# contador_geiger.net
KiCad netlist of a schematic drawn in Altium Designer
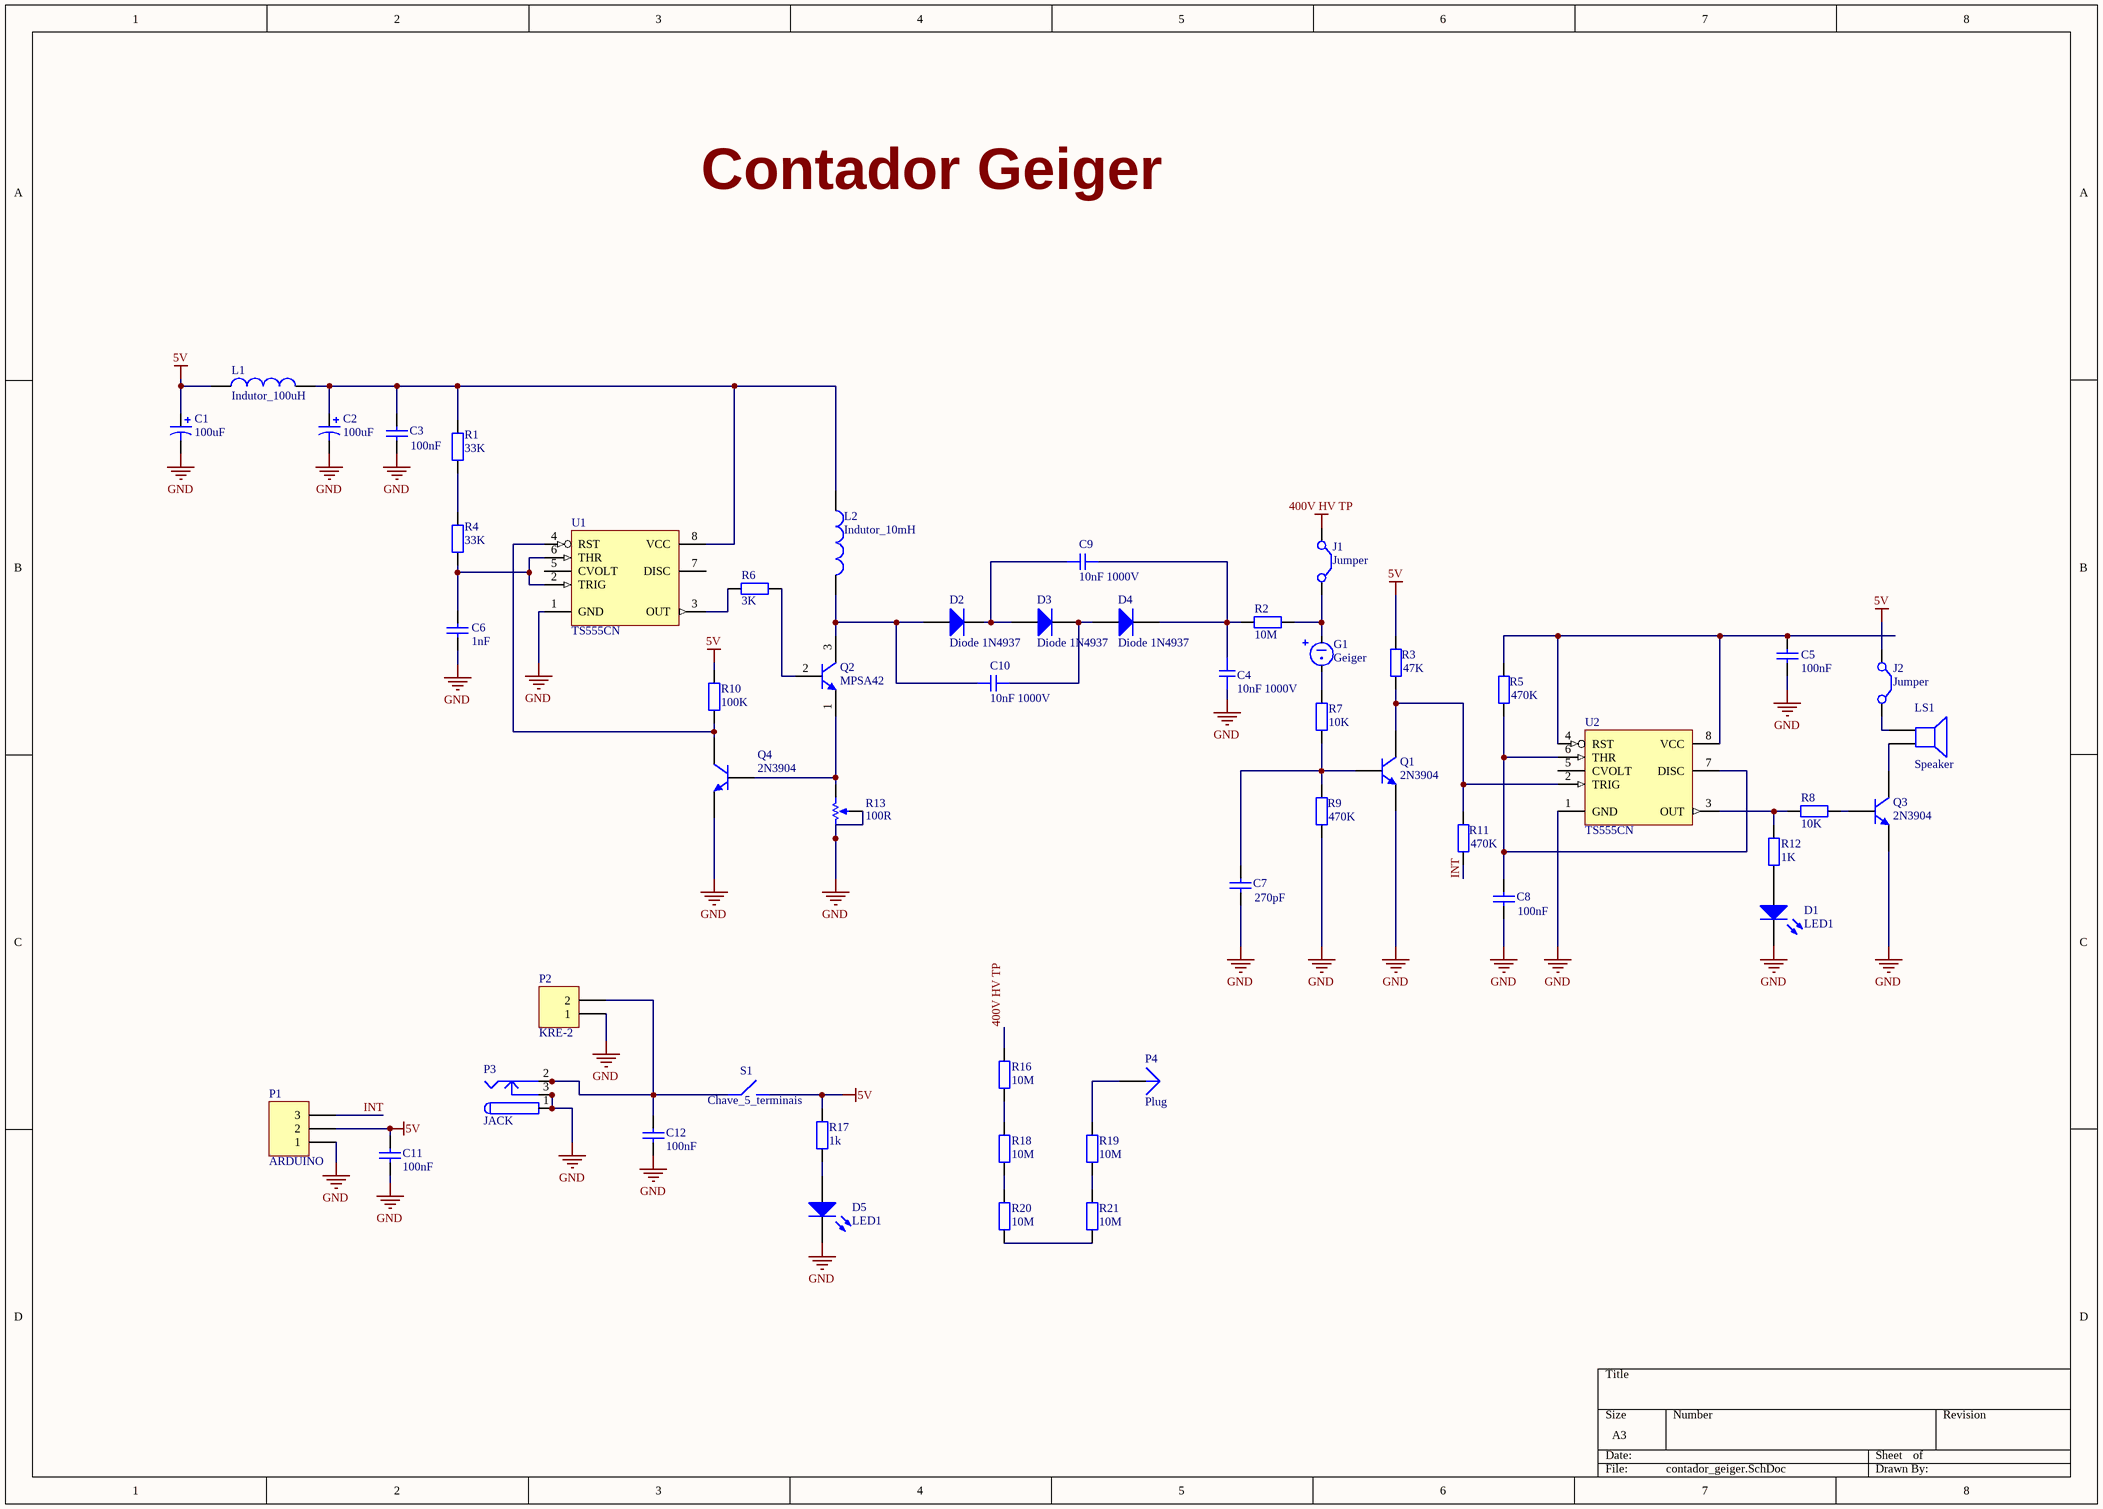
[diagram p0: contador_geiger.SchDoc]

(export (version "E")
  (design (tool "Eeschema 10.0.6"))
  (components
    (comp (ref "C1")
      (value "100uF")
      (footprint "RB7.6-15")
      (description "Polarized Capacitor (Radial)")
      (fields (field (name "Comment") "Cap Pol1") (field (name "PUBLISHER") "Altium Limited"))
      (libsource (lib "Miscellaneous Devices") (part "Cap Pol1"))
    )
    (comp (ref "C2")
      (value "100uF")
      (footprint "RB7.6-15")
      (description "Polarized Capacitor (Radial)")
      (fields (field (name "Comment") "Cap Pol1") (field (name "PUBLISHER") "Altium Limited"))
      (libsource (lib "Miscellaneous Devices") (part "Cap Pol1"))
    )
    (comp (ref "C3")
      (value "100nF")
      (footprint "RAD-0.3")
      (description "Capacitor")
      (fields (field (name "Comment") "Cap") (field (name "PUBLISHER") "Altium Limited"))
      (libsource (lib "Miscellaneous Devices") (part "Cap"))
    )
    (comp (ref "C4")
      (value "10nF 1000V")
      (footprint "Cap_10nF_1000V")
      (libsource (lib "Schlib1") (part "Capacitor_10n/1000V"))
    )
    (comp (ref "C5")
      (value "100nF")
      (footprint "RAD-0.3")
      (description "Capacitor")
      (fields (field (name "Comment") "Cap") (field (name "PUBLISHER") "Altium Limited"))
      (libsource (lib "Miscellaneous Devices") (part "Cap"))
    )
    (comp (ref "C6")
      (value "1nF")
      (footprint "RAD-0.3")
      (description "Capacitor")
      (fields (field (name "Comment") "Cap") (field (name "PUBLISHER") "Altium Limited"))
      (libsource (lib "Miscellaneous Devices") (part "Cap"))
    )
    (comp (ref "C7")
      (value "270pF")
      (footprint "RAD-0.3")
      (description "Capacitor")
      (fields (field (name "Comment") "Cap") (field (name "PUBLISHER") "Altium Limited"))
      (libsource (lib "Miscellaneous Devices") (part "Cap"))
    )
    (comp (ref "C8")
      (value "100nF")
      (footprint "RAD-0.3")
      (description "Capacitor")
      (fields (field (name "Comment") "Cap") (field (name "PUBLISHER") "Altium Limited"))
      (libsource (lib "Miscellaneous Devices") (part "Cap"))
    )
    (comp (ref "C9")
      (value "10nF 1000V")
      (footprint "Cap_10nF_1000V")
      (libsource (lib "Schlib1") (part "Capacitor_10n/1000V"))
    )
    (comp (ref "C10")
      (value "10nF 1000V")
      (footprint "Cap_10nF_1000V")
      (libsource (lib "Schlib1") (part "Capacitor_10n/1000V"))
    )
    (comp (ref "C11")
      (value "100nF")
      (footprint "RAD-0.3")
      (description "Capacitor")
      (fields (field (name "Comment") "Cap") (field (name "PUBLISHER") "Altium Limited"))
      (libsource (lib "Miscellaneous Devices") (part "Cap"))
    )
    (comp (ref "C12")
      (value "100nF")
      (footprint "RAD-0.3")
      (description "Capacitor")
      (fields (field (name "Comment") "Cap") (field (name "PUBLISHER") "Altium Limited"))
      (libsource (lib "Miscellaneous Devices") (part "Cap"))
    )
    (comp (ref "D1")
      (value "LED1")
      (footprint "LED-0")
      (description "Typical INFRARED GaAs LED")
      (fields (field (name "PUBLISHER") "Altium Limited"))
      (libsource (lib "Miscellaneous Devices") (part "LED0"))
    )
    (comp (ref "D2")
      (value "Diode 1N4937")
      (footprint "DO-41")
      (description "1 Amp Fast Recovery Rectifier")
      (fields (field (name "PUBLISHER") "Altium Limited"))
      (libsource (lib "Miscellaneous Devices") (part "Diode 1N4934"))
    )
    (comp (ref "D3")
      (value "Diode 1N4937")
      (footprint "DO-41")
      (description "1 Amp Fast Recovery Rectifier")
      (fields (field (name "PUBLISHER") "Altium Limited"))
      (libsource (lib "Miscellaneous Devices") (part "Diode 1N4934"))
    )
    (comp (ref "D4")
      (value "Diode 1N4937")
      (footprint "DO-41")
      (description "1 Amp Fast Recovery Rectifier")
      (fields (field (name "PUBLISHER") "Altium Limited"))
      (libsource (lib "Miscellaneous Devices") (part "Diode 1N4934"))
    )
    (comp (ref "D5")
      (value "LED1")
      (footprint "LED-0")
      (description "Typical INFRARED GaAs LED")
      (fields (field (name "PUBLISHER") "Altium Limited"))
      (libsource (lib "Miscellaneous Devices") (part "LED0"))
    )
    (comp (ref "G1")
      (value "Geiger")
      (footprint "Tubo Geiger")
      (libsource (lib "Schlib1") (part "Tubo_Geiger"))
    )
    (comp (ref "J1")
      (value "Jumper")
      (footprint "RAD-0.2")
      (description "Jumper Wire")
      (fields (field (name "PUBLISHER") "Altium Limited"))
      (libsource (lib "Miscellaneous Devices") (part "Jumper"))
    )
    (comp (ref "J2")
      (value "Jumper")
      (footprint "RAD-0.2")
      (description "Jumper Wire")
      (fields (field (name "PUBLISHER") "Altium Limited"))
      (libsource (lib "Miscellaneous Devices") (part "Jumper"))
    )
    (comp (ref "L1")
      (value "Indutor_100uH")
      (footprint "Indutor_100uH")
      (libsource (lib "Schlib1") (part "Indutor_100uH"))
    )
    (comp (ref "L2")
      (value "Indutor_10mH")
      (footprint "Indutor_10mH")
      (libsource (lib "Schlib1") (part "Indutor_10mH"))
    )
    (comp (ref "LS1")
      (value "Speaker")
      (footprint "PIN2")
      (description "Loudspeaker")
      (fields (field (name "PUBLISHER") "Altium Limited"))
      (libsource (lib "Miscellaneous Devices") (part "Speaker"))
    )
    (comp (ref "P1")
      (value "ARDUINO")
      (footprint "HDR1X3")
      (description "Header, 3-Pin")
      (fields (field (name "PUBLISHER") "Altium Limited"))
      (libsource (lib "Miscellaneous Connectors") (part "Header 3"))
    )
    (comp (ref "P2")
      (value "KRE-2")
      (footprint "HDR1X2")
      (description "Header, 2-Pin")
      (fields (field (name "PUBLISHER") "Altium Limited"))
      (libsource (lib "Miscellaneous Connectors") (part "Header 2"))
    )
    (comp (ref "P3")
      (value "JACK")
      (footprint "KLD-0202")
      (description "Low Voltage Power Supply Connector")
      (fields (field (name "PUBLISHER") "Altium Limited"))
      (libsource (lib "Miscellaneous Connectors") (part "PWR2.5"))
    )
    (comp (ref "P4")
      (value "Plug")
      (footprint "PIN1")
      (fields (field (name "PUBLISHER") "Altium Limited"))
      (libsource (lib "Miscellaneous Connectors") (part "Plug"))
    )
    (comp (ref "Q1")
      (value "2N3904")
      (footprint "TO-92A")
      (description "NPN General Purpose Amplifier")
      (fields (field (name "PUBLISHER") "Altium Limited"))
      (libsource (lib "Miscellaneous Devices") (part "2N3904"))
    )
    (comp (ref "Q2")
      (value "MPSA42")
      (footprint "ONSC-TO-92-3-29-11")
      (description "High Voltage Transistor, NPN Silicon, 3-Pin TO-92, Bulk Box")
      (fields (field (name "MANUFACTURER") "On Semiconductor"))
      (libsource (lib "ON Semi General Purpose Transistors") (part "MPSA42"))
    )
    (comp (ref "Q3")
      (value "2N3904")
      (footprint "TO-92A")
      (description "NPN General Purpose Amplifier")
      (fields (field (name "PUBLISHER") "Altium Limited"))
      (libsource (lib "Miscellaneous Devices") (part "2N3904"))
    )
    (comp (ref "Q4")
      (value "2N3904")
      (footprint "TO-92A")
      (description "NPN General Purpose Amplifier")
      (fields (field (name "PUBLISHER") "Altium Limited"))
      (libsource (lib "Miscellaneous Devices") (part "2N3904"))
    )
    (comp (ref "R1")
      (value "33K")
      (footprint "AXIAL-0.4")
      (description "Resistor")
      (fields (field (name "Comment") "Res2") (field (name "PUBLISHER") "Altium Limited"))
      (libsource (lib "Miscellaneous Devices") (part "Res2"))
    )
    (comp (ref "R2")
      (value "10M")
      (footprint "AXIAL-0.4")
      (description "Resistor")
      (fields (field (name "Comment") "Res2") (field (name "PUBLISHER") "Altium Limited"))
      (libsource (lib "") (part "Res2_2"))
    )
    (comp (ref "R3")
      (value "47K")
      (footprint "AXIAL-0.4")
      (description "Resistor")
      (fields (field (name "Comment") "Res2") (field (name "PUBLISHER") "Altium Limited"))
      (libsource (lib "Miscellaneous Devices") (part "Res2"))
    )
    (comp (ref "R4")
      (value "33K")
      (footprint "AXIAL-0.4")
      (description "Resistor")
      (fields (field (name "Comment") "Res2") (field (name "PUBLISHER") "Altium Limited"))
      (libsource (lib "Miscellaneous Devices") (part "Res2"))
    )
    (comp (ref "R5")
      (value "470K")
      (footprint "AXIAL-0.4")
      (description "Resistor")
      (fields (field (name "Comment") "Res2") (field (name "PUBLISHER") "Altium Limited"))
      (libsource (lib "Miscellaneous Devices") (part "Res2"))
    )
    (comp (ref "R6")
      (value "3K")
      (footprint "AXIAL-0.4")
      (description "Resistor")
      (fields (field (name "Comment") "Res2") (field (name "PUBLISHER") "Altium Limited"))
      (libsource (lib "") (part "Res2_2"))
    )
    (comp (ref "R7")
      (value "10K")
      (footprint "AXIAL-0.4")
      (description "Resistor")
      (fields (field (name "Comment") "Res2") (field (name "PUBLISHER") "Altium Limited"))
      (libsource (lib "Miscellaneous Devices") (part "Res2"))
    )
    (comp (ref "R8")
      (value "10K")
      (footprint "AXIAL-0.4")
      (description "Resistor")
      (fields (field (name "Comment") "Res2") (field (name "PUBLISHER") "Altium Limited"))
      (libsource (lib "") (part "Res2_1"))
    )
    (comp (ref "R9")
      (value "470K")
      (footprint "AXIAL-0.4")
      (description "Resistor")
      (fields (field (name "Comment") "Res2") (field (name "PUBLISHER") "Altium Limited"))
      (libsource (lib "Miscellaneous Devices") (part "Res2"))
    )
    (comp (ref "R10")
      (value "100K")
      (footprint "AXIAL-0.4")
      (description "Resistor")
      (fields (field (name "Comment") "Res2") (field (name "PUBLISHER") "Altium Limited"))
      (libsource (lib "Miscellaneous Devices") (part "Res2"))
    )
    (comp (ref "R11")
      (value "470K")
      (footprint "AXIAL-0.4")
      (description "Resistor")
      (fields (field (name "Comment") "Res2") (field (name "PUBLISHER") "Altium Limited"))
      (libsource (lib "Miscellaneous Devices") (part "Res2"))
    )
    (comp (ref "R12")
      (value "1K")
      (footprint "AXIAL-0.4")
      (description "Resistor")
      (fields (field (name "Comment") "Res2") (field (name "PUBLISHER") "Altium Limited"))
      (libsource (lib "Miscellaneous Devices") (part "Res2"))
    )
    (comp (ref "R13")
      (value "100R")
      (footprint "VR5")
      (description "Potentiometer")
      (fields (field (name "Comment") "RPot") (field (name "PUBLISHER") "Altium Limited"))
      (libsource (lib "Miscellaneous Devices") (part "RPot"))
    )
    (comp (ref "R16")
      (value "10M")
      (footprint "AXIAL-0.4")
      (description "Resistor")
      (fields (field (name "Comment") "Res2") (field (name "PUBLISHER") "Altium Limited"))
      (libsource (lib "Miscellaneous Devices") (part "Res2"))
    )
    (comp (ref "R17")
      (value "1k")
      (footprint "AXIAL-0.4")
      (description "Resistor")
      (fields (field (name "Comment") "Res2") (field (name "PUBLISHER") "Altium Limited"))
      (libsource (lib "Miscellaneous Devices") (part "Res2"))
    )
    (comp (ref "R18")
      (value "10M")
      (footprint "AXIAL-0.4")
      (description "Resistor")
      (fields (field (name "Comment") "Res2") (field (name "PUBLISHER") "Altium Limited"))
      (libsource (lib "Miscellaneous Devices") (part "Res2"))
    )
    (comp (ref "R19")
      (value "10M")
      (footprint "AXIAL-0.4")
      (description "Resistor")
      (fields (field (name "Comment") "Res2") (field (name "PUBLISHER") "Altium Limited"))
      (libsource (lib "Miscellaneous Devices") (part "Res2"))
    )
    (comp (ref "R20")
      (value "10M")
      (footprint "AXIAL-0.4")
      (description "Resistor")
      (fields (field (name "Comment") "Res2") (field (name "PUBLISHER") "Altium Limited"))
      (libsource (lib "Miscellaneous Devices") (part "Res2"))
    )
    (comp (ref "R21")
      (value "10M")
      (footprint "AXIAL-0.4")
      (description "Resistor")
      (fields (field (name "Comment") "Res2") (field (name "PUBLISHER") "Altium Limited"))
      (libsource (lib "Miscellaneous Devices") (part "Res2"))
    )
    (comp (ref "S1")
      (value "Chave_5_terminais")
      (footprint "Chave_5_terminais")
      (libsource (lib "Schlib1") (part "Chave_5_terminais"))
    )
    (comp (ref "U1")
      (value "TS555CN")
      (footprint "DIP8")
      (description "Low-Power Single CMOS Timer")
      (fields (field (name "PUBLISHER") "Altium Limited"))
      (libsource (lib "ST Analog Timer Circuit") (part "TS555CN"))
    )
    (comp (ref "U2")
      (value "TS555CN")
      (footprint "DIP8")
      (description "Low-Power Single CMOS Timer")
      (fields (field (name "PUBLISHER") "Altium Limited"))
      (libsource (lib "ST Analog Timer Circuit") (part "TS555CN"))
    )
  )
  (nets
    (net (code "1") (name "/INT") (class "Default")
      (node (ref "P1") (pin "3") (pinfunction "3_3") (pintype "passive"))
      (node (ref "R11") (pin "1") (pinfunction "1_1") (pintype "passive"))
    )
    (net (code "2") (name "5V") (class "Default")
      (node (ref "C1") (pin "1") (pinfunction "1_1") (pintype "passive"))
      (node (ref "C11") (pin "1") (pinfunction "1_1") (pintype "passive"))
      (node (ref "J2") (pin "1") (pinfunction "C1_1") (pintype "passive"))
      (node (ref "L1") (pin "1") (pinfunction "1_1") (pintype "passive"))
      (node (ref "P1") (pin "2") (pinfunction "2_2") (pintype "passive"))
      (node (ref "R10") (pin "2") (pinfunction "2_2") (pintype "passive"))
      (node (ref "R17") (pin "2") (pinfunction "2_2") (pintype "passive"))
      (node (ref "R3") (pin "2") (pinfunction "2_2") (pintype "passive"))
      (node (ref "S1") (pin "2") (pinfunction "2_2") (pintype "passive"))
    )
    (net (code "3") (name "400V HV TP") (class "Default")
      (node (ref "J1") (pin "1") (pinfunction "C1_1") (pintype "passive"))
      (node (ref "R16") (pin "2") (pinfunction "2_2") (pintype "passive"))
    )
    (net (code "4") (name "GND") (class "Default")
      (node (ref "C1") (pin "2") (pinfunction "2_2") (pintype "passive"))
      (node (ref "C11") (pin "2") (pinfunction "2_2") (pintype "passive"))
      (node (ref "C12") (pin "2") (pinfunction "2_2") (pintype "passive"))
      (node (ref "C2") (pin "2") (pinfunction "2_2") (pintype "passive"))
      (node (ref "C3") (pin "1") (pinfunction "1_1") (pintype "passive"))
      (node (ref "C4") (pin "1") (pinfunction "1_1") (pintype "passive"))
      (node (ref "C5") (pin "1") (pinfunction "1_1") (pintype "passive"))
      (node (ref "C6") (pin "1") (pinfunction "1_1") (pintype "passive"))
      (node (ref "C7") (pin "1") (pinfunction "1_1") (pintype "passive"))
      (node (ref "C8") (pin "1") (pinfunction "1_1") (pintype "passive"))
      (node (ref "D1") (pin "2") (pinfunction "K_2") (pintype "passive"))
      (node (ref "D5") (pin "2") (pinfunction "K_2") (pintype "passive"))
      (node (ref "P1") (pin "1") (pinfunction "1_1") (pintype "passive"))
      (node (ref "P2") (pin "1") (pinfunction "1_1") (pintype "passive"))
      (node (ref "P3") (pin "1") (pinfunction "1_1") (pintype "power_in"))
      (node (ref "P3") (pin "1A") (pinfunction "1A_1A") (pintype "power_in"))
      (node (ref "P3") (pin "1B") (pinfunction "1B_1B") (pintype "power_in"))
      (node (ref "P3") (pin "3") (pinfunction "3_3") (pintype "power_in"))
      (node (ref "P3") (pin "3A") (pinfunction "3A_3A") (pintype "power_in"))
      (node (ref "P3") (pin "3B") (pinfunction "3B_3B") (pintype "power_in"))
      (node (ref "Q1") (pin "1") (pinfunction "E_1") (pintype "passive"))
      (node (ref "Q3") (pin "1") (pinfunction "E_1") (pintype "passive"))
      (node (ref "Q4") (pin "1") (pinfunction "E_1") (pintype "passive"))
      (node (ref "R13") (pin "2") (pinfunction "BOT_2") (pintype "passive"))
      (node (ref "R13") (pin "3") (pinfunction "TAP_3") (pintype "passive"))
      (node (ref "R9") (pin "1") (pinfunction "1_1") (pintype "passive"))
      (node (ref "U1") (pin "1") (pinfunction "GND_1") (pintype "power_in"))
      (node (ref "U2") (pin "1") (pinfunction "GND_1") (pintype "power_in"))
    )
    (net (code "5") (name "Net-(C12-Pad1)") (class "Default")
      (node (ref "C12") (pin "1") (pinfunction "1_1") (pintype "passive"))
      (node (ref "P2") (pin "2") (pinfunction "2_2") (pintype "passive"))
      (node (ref "P3") (pin "2") (pinfunction "2_2") (pintype "power_in"))
      (node (ref "P3") (pin "2A") (pinfunction "2A_2A") (pintype "power_in"))
      (node (ref "P3") (pin "2B") (pinfunction "2B_2B") (pintype "power_in"))
      (node (ref "S1") (pin "1") (pinfunction "1_1") (pintype "passive"))
    )
    (net (code "6") (name "Net-(D1-A)") (class "Default")
      (node (ref "D1") (pin "1") (pinfunction "A_1") (pintype "passive"))
      (node (ref "R12") (pin "1") (pinfunction "1_1") (pintype "passive"))
    )
    (net (code "7") (name "Net-(D2-A)") (class "Default")
      (node (ref "C10") (pin "1") (pinfunction "1_1") (pintype "passive"))
      (node (ref "D2") (pin "1") (pinfunction "A_1") (pintype "passive"))
      (node (ref "L2") (pin "2") (pinfunction "2_2") (pintype "passive"))
      (node (ref "Q2") (pin "3") (pinfunction "C_3") (pintype "passive"))
    )
    (net (code "8") (name "Net-(D2-K)") (class "Default")
      (node (ref "C9") (pin "1") (pinfunction "1_1") (pintype "passive"))
      (node (ref "D2") (pin "2") (pinfunction "K_2") (pintype "passive"))
      (node (ref "D3") (pin "1") (pinfunction "A_1") (pintype "passive"))
    )
    (net (code "9") (name "Net-(D3-K)") (class "Default")
      (node (ref "C10") (pin "2") (pinfunction "2_2") (pintype "passive"))
      (node (ref "D3") (pin "2") (pinfunction "K_2") (pintype "passive"))
      (node (ref "D4") (pin "1") (pinfunction "A_1") (pintype "passive"))
    )
    (net (code "10") (name "Net-(D4-K)") (class "Default")
      (node (ref "C4") (pin "2") (pinfunction "2_2") (pintype "passive"))
      (node (ref "C9") (pin "2") (pinfunction "2_2") (pintype "passive"))
      (node (ref "D4") (pin "2") (pinfunction "K_2") (pintype "passive"))
      (node (ref "R2") (pin "2") (pinfunction "2_2") (pintype "passive"))
    )
    (net (code "11") (name "Net-(D5-A)") (class "Default")
      (node (ref "D5") (pin "1") (pinfunction "A_1") (pintype "passive"))
      (node (ref "R17") (pin "1") (pinfunction "1_1") (pintype "passive"))
    )
    (net (code "12") (name "Net-(G1-Pad2)") (class "Default")
      (node (ref "G1") (pin "2") (pinfunction "2_2") (pintype "passive"))
      (node (ref "R7") (pin "2") (pinfunction "2_2") (pintype "passive"))
    )
    (net (code "13") (name "Net-(J1-C2)") (class "Default")
      (node (ref "G1") (pin "1") (pinfunction "1_1") (pintype "passive"))
      (node (ref "J1") (pin "2") (pinfunction "C2_2") (pintype "passive"))
      (node (ref "R2") (pin "1") (pinfunction "1_1") (pintype "passive"))
    )
    (net (code "14") (name "Net-(J2-C2)") (class "Default")
      (node (ref "J2") (pin "2") (pinfunction "C2_2") (pintype "passive"))
      (node (ref "LS1") (pin "1") (pinfunction "1_1") (pintype "passive"))
    )
    (net (code "15") (name "Net-(P4-Pad1)") (class "Default")
      (node (ref "P4") (pin "1") (pinfunction "1_1") (pintype "passive"))
      (node (ref "R19") (pin "2") (pinfunction "2_2") (pintype "passive"))
    )
    (net (code "16") (name "Net-(Q1-B)") (class "Default")
      (node (ref "C7") (pin "2") (pinfunction "2_2") (pintype "passive"))
      (node (ref "Q1") (pin "2") (pinfunction "B_2") (pintype "passive"))
      (node (ref "R7") (pin "1") (pinfunction "1_1") (pintype "passive"))
      (node (ref "R9") (pin "2") (pinfunction "2_2") (pintype "passive"))
    )
    (net (code "17") (name "Net-(Q1-C)") (class "Default")
      (node (ref "Q1") (pin "3") (pinfunction "C_3") (pintype "passive"))
      (node (ref "R11") (pin "2") (pinfunction "2_2") (pintype "passive"))
      (node (ref "R3") (pin "1") (pinfunction "1_1") (pintype "passive"))
      (node (ref "U2") (pin "2") (pinfunction "TRIG_2") (pintype "input"))
    )
    (net (code "18") (name "Net-(Q2-B)") (class "Default")
      (node (ref "Q2") (pin "2") (pinfunction "B_2") (pintype "passive"))
      (node (ref "R6") (pin "1") (pinfunction "1_1") (pintype "passive"))
    )
    (net (code "19") (name "Net-(Q2-E)") (class "Default")
      (node (ref "Q2") (pin "1") (pinfunction "E_1") (pintype "passive"))
      (node (ref "Q4") (pin "2") (pinfunction "B_2") (pintype "passive"))
      (node (ref "R13") (pin "1") (pinfunction "TOP_1") (pintype "passive"))
    )
    (net (code "20") (name "Net-(Q3-B)") (class "Default")
      (node (ref "Q3") (pin "2") (pinfunction "B_2") (pintype "passive"))
      (node (ref "R8") (pin "2") (pinfunction "2_2") (pintype "passive"))
    )
    (net (code "21") (name "Net-(Q3-C)") (class "Default")
      (node (ref "LS1") (pin "2") (pinfunction "2_2") (pintype "passive"))
      (node (ref "Q3") (pin "3") (pinfunction "C_3") (pintype "passive"))
    )
    (net (code "22") (name "Net-(Q4-C)") (class "Default")
      (node (ref "Q4") (pin "3") (pinfunction "C_3") (pintype "passive"))
      (node (ref "R10") (pin "1") (pinfunction "1_1") (pintype "passive"))
      (node (ref "U1") (pin "4") (pinfunction "RST_4") (pintype "input"))
    )
    (net (code "23") (name "Net-(R1-Pad1)") (class "Default")
      (node (ref "R1") (pin "1") (pinfunction "1_1") (pintype "passive"))
      (node (ref "R4") (pin "2") (pinfunction "2_2") (pintype "passive"))
    )
    (net (code "24") (name "Net-(R16-Pad1)") (class "Default")
      (node (ref "R16") (pin "1") (pinfunction "1_1") (pintype "passive"))
      (node (ref "R18") (pin "2") (pinfunction "2_2") (pintype "passive"))
    )
    (net (code "25") (name "Net-(R18-Pad1)") (class "Default")
      (node (ref "R18") (pin "1") (pinfunction "1_1") (pintype "passive"))
      (node (ref "R20") (pin "2") (pinfunction "2_2") (pintype "passive"))
    )
    (net (code "26") (name "Net-(R19-Pad1)") (class "Default")
      (node (ref "R19") (pin "1") (pinfunction "1_1") (pintype "passive"))
      (node (ref "R21") (pin "2") (pinfunction "2_2") (pintype "passive"))
    )
    (net (code "27") (name "Net-(R20-Pad1)") (class "Default")
      (node (ref "R20") (pin "1") (pinfunction "1_1") (pintype "passive"))
      (node (ref "R21") (pin "1") (pinfunction "1_1") (pintype "passive"))
    )
    (net (code "28") (name "Net-(U1-OUT)") (class "Default")
      (node (ref "R6") (pin "2") (pinfunction "2_2") (pintype "passive"))
      (node (ref "U1") (pin "3") (pinfunction "OUT_3") (pintype "output"))
    )
    (net (code "29") (name "Net-(U1-THR)") (class "Default")
      (node (ref "C6") (pin "2") (pinfunction "2_2") (pintype "passive"))
      (node (ref "R4") (pin "1") (pinfunction "1_1") (pintype "passive"))
      (node (ref "U1") (pin "2") (pinfunction "TRIG_2") (pintype "input"))
      (node (ref "U1") (pin "6") (pinfunction "THR_6") (pintype "input"))
    )
    (net (code "30") (name "Net-(U1-VCC)") (class "Default")
      (node (ref "C2") (pin "1") (pinfunction "1_1") (pintype "passive"))
      (node (ref "C3") (pin "2") (pinfunction "2_2") (pintype "passive"))
      (node (ref "L1") (pin "2") (pinfunction "2_2") (pintype "passive"))
      (node (ref "L2") (pin "1") (pinfunction "1_1") (pintype "passive"))
      (node (ref "R1") (pin "2") (pinfunction "2_2") (pintype "passive"))
      (node (ref "U1") (pin "8") (pinfunction "VCC_8") (pintype "power_in"))
    )
    (net (code "31") (name "Net-(U2-DISC)") (class "Default")
      (node (ref "C8") (pin "2") (pinfunction "2_2") (pintype "passive"))
      (node (ref "R5") (pin "1") (pinfunction "1_1") (pintype "passive"))
      (node (ref "U2") (pin "6") (pinfunction "THR_6") (pintype "input"))
      (node (ref "U2") (pin "7") (pinfunction "DISC_7") (pintype "open_collector"))
    )
    (net (code "32") (name "Net-(U2-OUT)") (class "Default")
      (node (ref "R12") (pin "2") (pinfunction "2_2") (pintype "passive"))
      (node (ref "R8") (pin "1") (pinfunction "1_1") (pintype "passive"))
      (node (ref "U2") (pin "3") (pinfunction "OUT_3") (pintype "output"))
    )
    (net (code "33") (name "Net-(U2-RST)") (class "Default")
      (node (ref "C5") (pin "2") (pinfunction "2_2") (pintype "passive"))
      (node (ref "R5") (pin "2") (pinfunction "2_2") (pintype "passive"))
      (node (ref "U2") (pin "4") (pinfunction "RST_4") (pintype "input"))
      (node (ref "U2") (pin "8") (pinfunction "VCC_8") (pintype "power_in"))
    )
    (net (code "34") (name "unconnected-(U1-CVOLT-Pad5)") (class "Default")
      (node (ref "U1") (pin "5") (pinfunction "CVOLT_5") (pintype "passive"))
    )
    (net (code "35") (name "unconnected-(U1-DISC-Pad7)") (class "Default")
      (node (ref "U1") (pin "7") (pinfunction "DISC_7") (pintype "open_collector"))
    )
    (net (code "36") (name "unconnected-(U2-CVOLT-Pad5)") (class "Default")
      (node (ref "U2") (pin "5") (pinfunction "CVOLT_5") (pintype "passive"))
    )
  )
)
